# USBC_A.net
KiCad netlist of a schematic drawn in Altium Designer
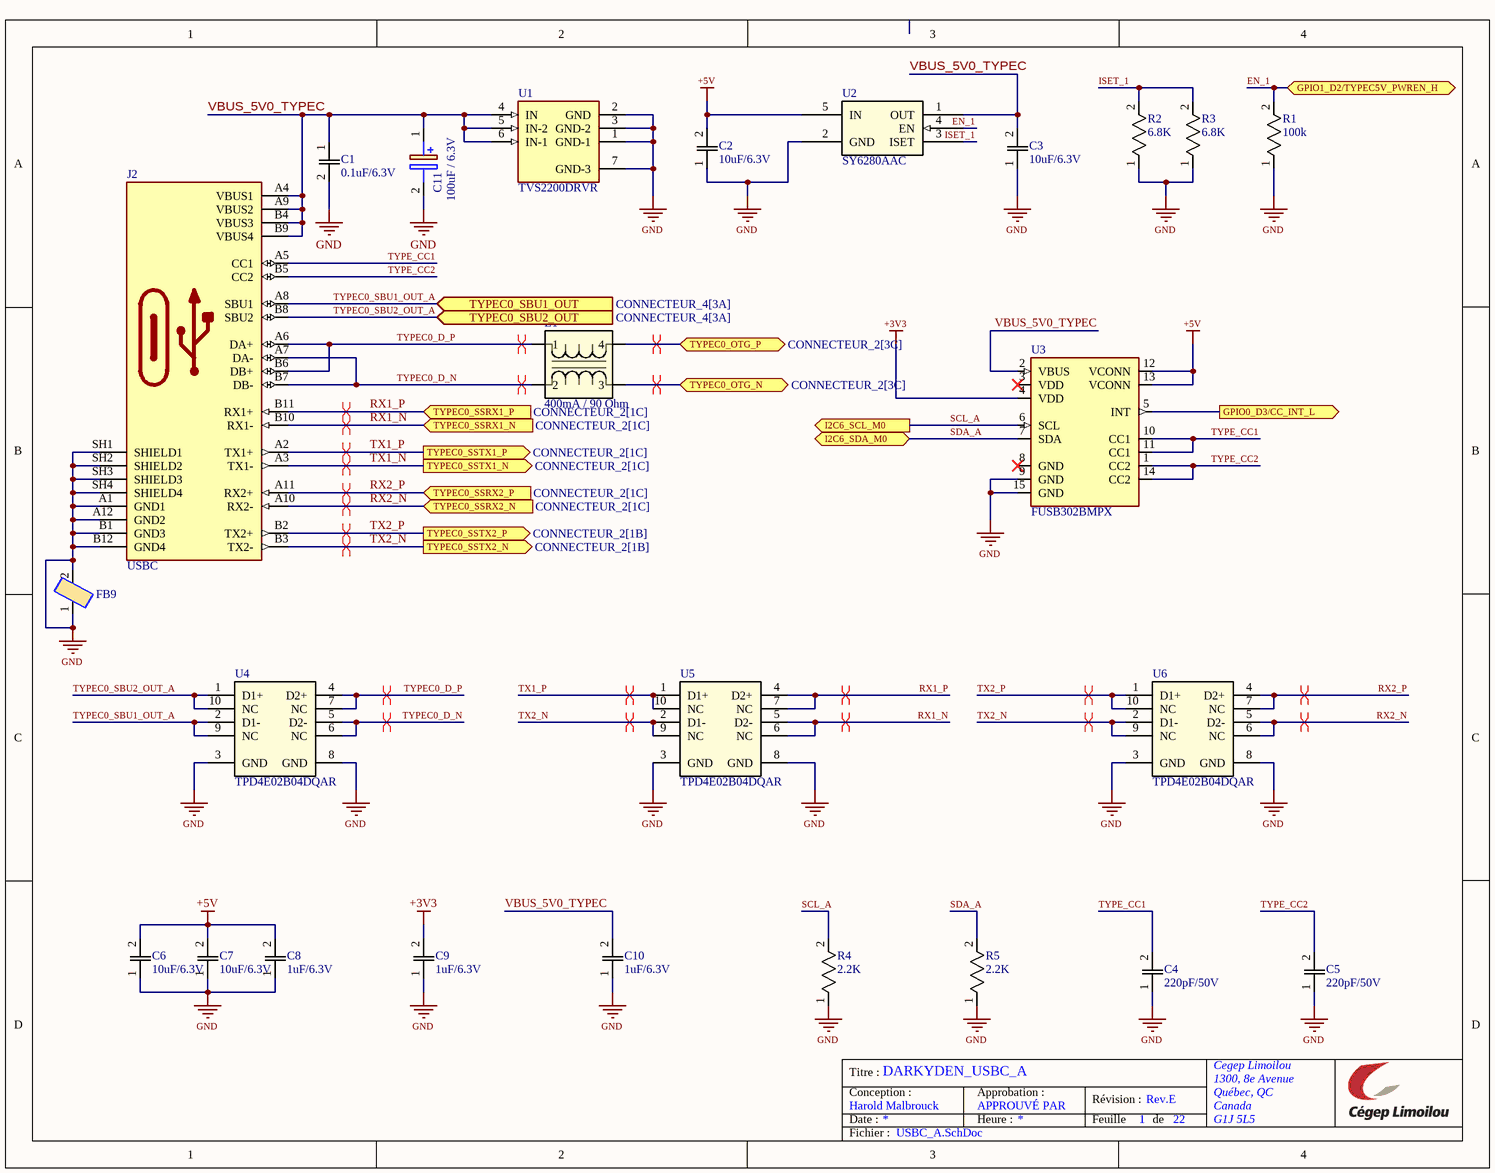
[diagram p0: USBC_A.SchDoc]

(export (version "E")
  (design (tool "Eeschema 10.0.6"))
  (components
    (comp (ref "C1")
      (value "0.1uF/6.3V")
      (footprint "SamacSys:C0805")
      (description "0.1uF 6.3V X7R 10% Pad SMD 0805 125C T/R")
      (fields
        (field (name "MANUFACTURER_PART_NUMBER") "C0805C104K9RACTU")
        (field (name "MOUSER PART NUMBER") "80-C0805C104K9R")
      )
      (libsource (lib "SamacSys") (part "C0805C104K9RACTU"))
    )
    (comp (ref "C2")
      (value "10uF/6.3V")
      (footprint "SamacSys:C0805")
      (fields
        (field (name "MANUFACTURER_PART_NUMBER") "C0805C106K9RACTU")
        (field (name "MOUSER PART NUMBER") "80-C0805C106K9R")
        (field (name "MANUFACTURER") "KEMET")
      )
      (libsource (lib "SamacSys") (part "C0805C106K9RACTU"))
    )
    (comp (ref "C3")
      (value "10uF/6.3V")
      (footprint "SamacSys:C0805")
      (fields
        (field (name "MANUFACTURER_PART_NUMBER") "C0805C106K9RACTU")
        (field (name "MOUSER PART NUMBER") "80-C0805C106K9R")
        (field (name "MANUFACTURER") "KEMET")
      )
      (libsource (lib "SamacSys") (part "C0805C106K9RACTU"))
    )
    (comp (ref "C4")
      (value "220pF/50V")
      (footprint "CAPC220145_88N_KEM")
      (description "Cap Ceramic 220pF 50V X7R 20% Pad SMD 0805 125C T/R")
      (fields
        (field (name "MANUFACTURER") "KEMET")
        (field (name "MANUFACTURER PART NUMBER") "C0805C221M5RACTU")
      )
      (libsource (lib "C0805C221M5RACTU") (part "C0805C221M5RACTU"))
    )
    (comp (ref "C5")
      (value "220pF/50V")
      (footprint "CAPC220145_88N_KEM")
      (description "Cap Ceramic 220pF 50V X7R 20% Pad SMD 0805 125C T/R")
      (fields
        (field (name "MANUFACTURER") "KEMET")
        (field (name "MANUFACTURER PART NUMBER") "C0805C221M5RACTU")
      )
      (libsource (lib "C0805C221M5RACTU") (part "C0805C221M5RACTU"))
    )
    (comp (ref "C6")
      (value "10uF/6.3V")
      (footprint "SamacSys:C0805")
      (fields
        (field (name "MANUFACTURER_PART_NUMBER") "C0805C106K9RACTU")
        (field (name "MOUSER PART NUMBER") "80-C0805C106K9R")
        (field (name "MANUFACTURER") "KEMET")
      )
      (libsource (lib "SamacSys") (part "C0805C106K9RACTU"))
    )
    (comp (ref "C7")
      (value "10uF/6.3V")
      (footprint "SamacSys:C0805")
      (fields
        (field (name "MANUFACTURER_PART_NUMBER") "C0805C106K9RACTU")
        (field (name "MOUSER PART NUMBER") "80-C0805C106K9R")
        (field (name "MANUFACTURER") "KEMET")
      )
      (libsource (lib "SamacSys") (part "C0805C106K9RACTU"))
    )
    (comp (ref "C8")
      (value "1uF/6.3V")
      (footprint "SamacSys:C0805")
      (description "1 uF, 6.3 V, ± 10%, X7R, 0805 [2012 Metric] Multilayer Ceramic Capacitor,")
      (fields
        (field (name "MANUFACTURER_PART_NUMBER") "C0805C105K9RACTU")
        (field (name "MOUSER PART NUMBER") "80-C0805C105K9R")
      )
      (libsource (lib "SamacSys") (part "C0805C105K9RACTU"))
    )
    (comp (ref "C9")
      (value "1uF/6.3V")
      (footprint "SamacSys:C0805")
      (description "1 uF, 6.3 V, ± 10%, X7R, 0805 [2012 Metric] Multilayer Ceramic Capacitor,")
      (fields
        (field (name "MANUFACTURER_PART_NUMBER") "C0805C105K9RACTU")
        (field (name "MOUSER PART NUMBER") "80-C0805C105K9R")
      )
      (libsource (lib "SamacSys") (part "C0805C105K9RACTU"))
    )
    (comp (ref "C10")
      (value "1uF/6.3V")
      (footprint "SamacSys:C0805")
      (description "1 uF, 6.3 V, ± 10%, X7R, 0805 [2012 Metric] Multilayer Ceramic Capacitor,")
      (fields
        (field (name "MANUFACTURER_PART_NUMBER") "C0805C105K9RACTU")
        (field (name "MOUSER PART NUMBER") "80-C0805C105K9R")
      )
      (libsource (lib "SamacSys") (part "C0805C105K9RACTU"))
    )
    (comp (ref "C11")
      (value "100uF / 6.3V")
      (footprint "SamacSys:EEE0GA101SR")
      (description "100uF 6.3V 20% Cap Aluminum Lytic  SMD 0.36 Ohm 240mA 2000h 105C Automotive T/R")
      (fields
        (field (name "MANUFACTURER_PART_NUMBER") "EEE-FPJ101UAR")
        (field (name "MOUSER PART NUMBER") "667-EEE-FPJ101UAR")
      )
      (libsource (lib "SamacSys") (part "EEE-FPJ101UAR"))
    )
    (comp (ref "FB9")
      (value "220R / 100MHz")
      (footprint "SamacSys:BLM18SP221SN1B")
      (description "Ferrite Beads Multi-Layer 220Ohm 25% 100MHz 2A 50mOhm DCR 0603 Paper T/R")
      (fields
        (field (name "MANUFACTURER_PART_NUMBER") "BLM18EG221SN1D")
        (field (name "MOUSER PART NUMBER") "81-BLM18EG221SN1D")
      )
      (libsource (lib "SamacSys") (part "BLM18EG221SN1D"))
    )
    (comp (ref "J2")
      (value "USBC")
      (footprint "MOLEX_2012670005")
      (fields (field (name "MF") "Molex") (field (name "MP") "2012670005"))
      (libsource (lib "USBC") (part "USBC"))
    )
    (comp (ref "L1")
      (value "400mA / 90 Ohm")
      (footprint "SamacSys:ACM20129002PT002")
      (description "Ferrite Beads Wirewound Common Mode Filter 90Ohm 100MHz 400mA 0805 T/R")
      (fields
        (field (name "MANUFACTURER_PART_NUMBER") "ACM2012-900-2P-T002")
        (field (name "MOUSER PART NUMBER") "810-ACM20129002PT002")
      )
      (libsource (lib "SamacSys") (part "ACM2012-900-2P-T002"))
    )
    (comp (ref "R1")
      (value "100k")
      (footprint "SamacSys:ERJ3EKF1000V")
      (description "100K Ohm 5%  Res Thick Film 0603 1/10W +/-200ppm/ßC Molded SMD Punched Carrier T/R")
      (fields
        (field (name "MANUFACTURER_PART_NUMBER") "ERJ-3GEYJ104V")
        (field (name "MOUSER PART NUMBER") "667-ERJ-3GEYJ104V")
      )
      (libsource (lib "SamacSys") (part "ERJ-3GEYJ104V"))
    )
    (comp (ref "R2")
      (value "6.8K")
      (footprint "SamacSys:ERJ3EKF1000V")
      (description "6.8 kOhm, ± 5%, 100 mW, 0603 [1608 Metric], Thick Film, General Purpose")
      (fields
        (field (name "MANUFACTURER_PART_NUMBER") "ERJ-3GEYJ682V")
        (field (name "MANUFACTURER") "Panasonic")
      )
      (libsource (lib "SamacSys") (part "ERJ-3GEYJ682V"))
    )
    (comp (ref "R3")
      (value "6.8K")
      (footprint "SamacSys:ERJ3EKF1000V")
      (description "6.8 kOhm, ± 5%, 100 mW, 0603 [1608 Metric], Thick Film, General Purpose")
      (fields
        (field (name "MANUFACTURER_PART_NUMBER") "ERJ-3GEYJ682V")
        (field (name "MANUFACTURER") "Panasonic")
      )
      (libsource (lib "SamacSys") (part "ERJ-3GEYJ682V"))
    )
    (comp (ref "R4")
      (value "2.2K")
      (footprint "SamacSys:ERJ3EKF1000V")
      (description "2.2 kOhm, ï¿½ 5%, 100 mW, 0603 [1608 Metric], Thick Film, General Purpose")
      (fields
        (field (name "MANUFACTURER_PART_NUMBER") "ERJ-3GEYJ222V")
        (field (name "MOUSER PART NUMBER") "667-ERJ-3GEYJ222V")
      )
      (libsource (lib "SamacSys") (part "ERJ-3GEYJ222V"))
    )
    (comp (ref "R5")
      (value "2.2K")
      (footprint "SamacSys:ERJ3EKF1000V")
      (description "2.2 kOhm, ï¿½ 5%, 100 mW, 0603 [1608 Metric], Thick Film, General Purpose")
      (fields
        (field (name "MANUFACTURER_PART_NUMBER") "ERJ-3GEYJ222V")
        (field (name "MOUSER PART NUMBER") "667-ERJ-3GEYJ222V")
      )
      (libsource (lib "SamacSys") (part "ERJ-3GEYJ222V"))
    )
    (comp (ref "U1")
      (value "TVS2200DRVR")
      (footprint "SON65P200X200X80-7N")
      (description "ESD Suppressors / TVS Diodes 22V flat-clamp surge protection device 6-WSON -40 to 125")
      (fields (field (name "MF") "Texas Instruments"))
      (libsource (lib "TVS2200") (part "TVS2200DRVR"))
    )
    (comp (ref "U2")
      (value "SY6280AAC")
      (footprint "SamacSys:SOT95P285X140-5N")
      (description "2.4V~5.5V 80mΩ Active High 1 High-side switch SOT-23-5 Power Distribution Switches ROHS")
      (libsource (lib "SamacSys") (part "SY6280AAC"))
    )
    (comp (ref "U3")
      (value "FUSB302BMPX")
      (footprint "SamacSys:QFN50P250X250X80-15N")
      (description "USB Controller USB 3.1 USB Interface 14-MLP (2.5x2.5)")
      (fields (field (name "MOUSER PART NUMBER") "512-FUSB302BMPX"))
      (libsource (lib "SamacSys") (part "FUSB302BMPX"))
    )
    (comp (ref "U4")
      (value "TPD4E02B04DQAR")
      (footprint "DQA0010A")
      (description "TVS DIODE 3.6V 8.8V 10USON / 4-Channel ESD Protection Diode for USB Type-C and HDMI 2.0")
      (fields (field (name "MANUFACTURER") "Texas Instruments"))
      (libsource (lib "TPD4E02B04DQAR") (part "TPD4E02B04DQAR"))
    )
    (comp (ref "U5")
      (value "TPD4E02B04DQAR")
      (footprint "DQA0010A")
      (description "TVS DIODE 3.6V 8.8V 10USON / 4-Channel ESD Protection Diode for USB Type-C and HDMI 2.0")
      (fields (field (name "MANUFACTURER") "Texas Instruments"))
      (libsource (lib "TPD4E02B04DQAR") (part "TPD4E02B04DQAR"))
    )
    (comp (ref "U6")
      (value "TPD4E02B04DQAR")
      (footprint "DQA0010A")
      (description "TVS DIODE 3.6V 8.8V 10USON / 4-Channel ESD Protection Diode for USB Type-C and HDMI 2.0")
      (fields (field (name "MANUFACTURER") "Texas Instruments"))
      (libsource (lib "TPD4E02B04DQAR") (part "TPD4E02B04DQAR"))
    )
  )
  (nets
    (net (code "1") (name "+3V3") (class "Default")
      (node (ref "C9") (pin "2") (pinfunction "2_2") (pintype "passive"))
      (node (ref "U3") (pin "4") (pinfunction "VDD_4") (pintype "power_in"))
    )
    (net (code "2") (name "+5V") (class "Default")
      (node (ref "C2") (pin "2") (pinfunction "2_2") (pintype "passive"))
      (node (ref "C6") (pin "2") (pinfunction "2_2") (pintype "passive"))
      (node (ref "C7") (pin "2") (pinfunction "2_2") (pintype "passive"))
      (node (ref "C8") (pin "2") (pinfunction "2_2") (pintype "passive"))
      (node (ref "U2") (pin "5") (pinfunction "IN_5") (pintype "power_in"))
      (node (ref "U3") (pin "12") (pinfunction "VCONN_12") (pintype "power_in"))
      (node (ref "U3") (pin "13") (pinfunction "VCONN_13") (pintype "power_in"))
    )
    (net (code "3") (name "/EN_1") (class "Default")
      (node (ref "R1") (pin "2") (pinfunction "2_2") (pintype "passive"))
      (node (ref "U2") (pin "4") (pinfunction "EN_4") (pintype "input"))
    )
    (net (code "4") (name "/GPIO0_D3{slash}CC_INT_L") (class "Default")
      (node (ref "U3") (pin "5") (pinfunction "INT_5") (pintype "output"))
    )
    (net (code "5") (name "/ISET_1") (class "Default")
      (node (ref "R2") (pin "2") (pinfunction "2_2") (pintype "passive"))
      (node (ref "R3") (pin "2") (pinfunction "2_2") (pintype "passive"))
      (node (ref "U2") (pin "3") (pinfunction "ISET_3") (pintype "passive"))
    )
    (net (code "6") (name "/RX1_N") (class "Default")
      (node (ref "J2") (pin "B10") (pinfunction "RX1-_B10") (pintype "input"))
      (node (ref "U5") (pin "5") (pinfunction "D2-_5") (pintype "passive"))
      (node (ref "U5") (pin "6") (pinfunction "NC_6") (pintype "passive"))
    )
    (net (code "7") (name "/RX1_P") (class "Default")
      (node (ref "J2") (pin "B11") (pinfunction "RX1+_B11") (pintype "input"))
      (node (ref "U5") (pin "4") (pinfunction "D2+_4") (pintype "passive"))
      (node (ref "U5") (pin "7") (pinfunction "NC_7") (pintype "passive"))
    )
    (net (code "8") (name "/RX2_N") (class "Default")
      (node (ref "J2") (pin "A10") (pinfunction "RX2-_A10") (pintype "input"))
      (node (ref "U6") (pin "5") (pinfunction "D2-_5") (pintype "passive"))
      (node (ref "U6") (pin "6") (pinfunction "NC_6") (pintype "passive"))
    )
    (net (code "9") (name "/RX2_P") (class "Default")
      (node (ref "J2") (pin "A11") (pinfunction "RX2+_A11") (pintype "input"))
      (node (ref "U6") (pin "4") (pinfunction "D2+_4") (pintype "passive"))
      (node (ref "U6") (pin "7") (pinfunction "NC_7") (pintype "passive"))
    )
    (net (code "10") (name "/SCL_A") (class "Default")
      (node (ref "R4") (pin "2") (pinfunction "2_2") (pintype "passive"))
      (node (ref "U3") (pin "6") (pinfunction "SCL_6") (pintype "input"))
    )
    (net (code "11") (name "/SDA_A") (class "Default")
      (node (ref "R5") (pin "2") (pinfunction "2_2") (pintype "passive"))
      (node (ref "U3") (pin "7") (pinfunction "SDA_7") (pintype "bidirectional"))
    )
    (net (code "12") (name "/TX1_N") (class "Default")
      (node (ref "J2") (pin "A3") (pinfunction "TX1-_A3") (pintype "output"))
    )
    (net (code "13") (name "/TX1_P") (class "Default")
      (node (ref "J2") (pin "A2") (pinfunction "TX1+_A2") (pintype "output"))
      (node (ref "U5") (pin "1") (pinfunction "D1+_1") (pintype "passive"))
      (node (ref "U5") (pin "10") (pinfunction "NC_10") (pintype "passive"))
    )
    (net (code "14") (name "/TX2_N") (class "Default")
      (node (ref "J2") (pin "B3") (pinfunction "TX2-_B3") (pintype "output"))
      (node (ref "U5") (pin "2") (pinfunction "D1-_2") (pintype "passive"))
      (node (ref "U5") (pin "9") (pinfunction "NC_9") (pintype "passive"))
      (node (ref "U6") (pin "2") (pinfunction "D1-_2") (pintype "passive"))
      (node (ref "U6") (pin "9") (pinfunction "NC_9") (pintype "passive"))
    )
    (net (code "15") (name "/TX2_P") (class "Default")
      (node (ref "J2") (pin "B2") (pinfunction "TX2+_B2") (pintype "output"))
      (node (ref "U6") (pin "1") (pinfunction "D1+_1") (pintype "passive"))
      (node (ref "U6") (pin "10") (pinfunction "NC_10") (pintype "passive"))
    )
    (net (code "16") (name "/TYPEC0_D_N") (class "Default")
      (node (ref "J2") (pin "A7") (pinfunction "DA-_A7") (pintype "bidirectional"))
      (node (ref "J2") (pin "B7") (pinfunction "DB-_B7") (pintype "bidirectional"))
      (node (ref "L1") (pin "2") (pinfunction "2_2") (pintype "passive"))
      (node (ref "U4") (pin "5") (pinfunction "D2-_5") (pintype "passive"))
      (node (ref "U4") (pin "6") (pinfunction "NC_6") (pintype "passive"))
    )
    (net (code "17") (name "/TYPEC0_D_P") (class "Default")
      (node (ref "J2") (pin "A6") (pinfunction "DA+_A6") (pintype "bidirectional"))
      (node (ref "J2") (pin "B6") (pinfunction "DB+_B6") (pintype "bidirectional"))
      (node (ref "L1") (pin "1") (pinfunction "1_1") (pintype "passive"))
      (node (ref "U4") (pin "4") (pinfunction "D2+_4") (pintype "passive"))
      (node (ref "U4") (pin "7") (pinfunction "NC_7") (pintype "passive"))
    )
    (net (code "18") (name "/TYPEC0_OTG_N") (class "Default")
      (node (ref "L1") (pin "3") (pinfunction "3_3") (pintype "passive"))
    )
    (net (code "19") (name "/TYPEC0_OTG_P") (class "Default")
      (node (ref "L1") (pin "4") (pinfunction "4_4") (pintype "passive"))
    )
    (net (code "20") (name "/TYPEC0_SBU1_OUT_A") (class "Default")
      (node (ref "J2") (pin "A8") (pinfunction "SBU1_A8") (pintype "bidirectional"))
      (node (ref "U4") (pin "2") (pinfunction "D1-_2") (pintype "passive"))
      (node (ref "U4") (pin "9") (pinfunction "NC_9") (pintype "passive"))
    )
    (net (code "21") (name "/TYPEC0_SBU2_OUT_A") (class "Default")
      (node (ref "J2") (pin "B8") (pinfunction "SBU2_B8") (pintype "bidirectional"))
      (node (ref "U4") (pin "1") (pinfunction "D1+_1") (pintype "passive"))
      (node (ref "U4") (pin "10") (pinfunction "NC_10") (pintype "passive"))
    )
    (net (code "22") (name "/TYPE_CC1") (class "Default")
      (node (ref "C4") (pin "2") (pinfunction "2_2") (pintype "passive"))
      (node (ref "J2") (pin "A5") (pinfunction "CC1_A5") (pintype "bidirectional"))
      (node (ref "U3") (pin "10") (pinfunction "CC1_10") (pintype "bidirectional"))
      (node (ref "U3") (pin "11") (pinfunction "CC1_11") (pintype "bidirectional"))
    )
    (net (code "23") (name "/TYPE_CC2") (class "Default")
      (node (ref "C5") (pin "2") (pinfunction "2_2") (pintype "passive"))
      (node (ref "J2") (pin "B5") (pinfunction "CC2_B5") (pintype "bidirectional"))
      (node (ref "U3") (pin "1") (pinfunction "CC2_1") (pintype "bidirectional"))
      (node (ref "U3") (pin "14") (pinfunction "CC2_14") (pintype "bidirectional"))
    )
    (net (code "24") (name "/VBUS_5V0_TYPEC") (class "Default")
      (node (ref "C1") (pin "1") (pinfunction "1_1") (pintype "passive"))
      (node (ref "C10") (pin "2") (pinfunction "2_2") (pintype "passive"))
      (node (ref "C11") (pin "1") (pinfunction "+_1") (pintype "passive"))
      (node (ref "C3") (pin "2") (pinfunction "2_2") (pintype "passive"))
      (node (ref "J2") (pin "A4") (pinfunction "VBUS1_A4") (pintype "power_in"))
      (node (ref "J2") (pin "A9") (pinfunction "VBUS2_A9") (pintype "power_in"))
      (node (ref "J2") (pin "B4") (pinfunction "VBUS3_B4") (pintype "power_in"))
      (node (ref "J2") (pin "B9") (pinfunction "VBUS4_B9") (pintype "power_in"))
      (node (ref "U1") (pin "4") (pinfunction "IN_4") (pintype "input"))
      (node (ref "U1") (pin "5") (pinfunction "IN-2_5") (pintype "input"))
      (node (ref "U1") (pin "6") (pinfunction "IN-1_6") (pintype "input"))
      (node (ref "U2") (pin "1") (pinfunction "OUT_1") (pintype "power_in"))
      (node (ref "U3") (pin "2") (pinfunction "VBUS_2") (pintype "input"))
    )
    (net (code "25") (name "GND") (class "Default")
      (node (ref "C1") (pin "2") (pinfunction "2_2") (pintype "passive"))
      (node (ref "C10") (pin "1") (pinfunction "1_1") (pintype "passive"))
      (node (ref "C11") (pin "2") (pinfunction "-_2") (pintype "passive"))
      (node (ref "C2") (pin "1") (pinfunction "1_1") (pintype "passive"))
      (node (ref "C3") (pin "1") (pinfunction "1_1") (pintype "passive"))
      (node (ref "C4") (pin "1") (pinfunction "1_1") (pintype "passive"))
      (node (ref "C5") (pin "1") (pinfunction "1_1") (pintype "passive"))
      (node (ref "C6") (pin "1") (pinfunction "1_1") (pintype "passive"))
      (node (ref "C7") (pin "1") (pinfunction "1_1") (pintype "passive"))
      (node (ref "C8") (pin "1") (pinfunction "1_1") (pintype "passive"))
      (node (ref "C9") (pin "1") (pinfunction "1_1") (pintype "passive"))
      (node (ref "FB9") (pin "1") (pinfunction "1_1") (pintype "passive"))
      (node (ref "FB9") (pin "2") (pinfunction "2_2") (pintype "passive"))
      (node (ref "J2") (pin "A1") (pinfunction "GND1_A1") (pintype "passive"))
      (node (ref "J2") (pin "A12") (pinfunction "GND2_A12") (pintype "passive"))
      (node (ref "J2") (pin "B1") (pinfunction "GND3_B1") (pintype "passive"))
      (node (ref "J2") (pin "B12") (pinfunction "GND4_B12") (pintype "passive"))
      (node (ref "J2") (pin "SH1") (pinfunction "SHIELD1_SH1") (pintype "passive"))
      (node (ref "J2") (pin "SH2") (pinfunction "SHIELD2_SH2") (pintype "passive"))
      (node (ref "J2") (pin "SH3") (pinfunction "SHIELD3_SH3") (pintype "passive"))
      (node (ref "J2") (pin "SH4") (pinfunction "SHIELD4_SH4") (pintype "passive"))
      (node (ref "R1") (pin "1") (pinfunction "1_1") (pintype "passive"))
      (node (ref "R2") (pin "1") (pinfunction "1_1") (pintype "passive"))
      (node (ref "R3") (pin "1") (pinfunction "1_1") (pintype "passive"))
      (node (ref "R4") (pin "1") (pinfunction "1_1") (pintype "passive"))
      (node (ref "R5") (pin "1") (pinfunction "1_1") (pintype "passive"))
      (node (ref "U1") (pin "1") (pinfunction "GND-1_1") (pintype "passive"))
      (node (ref "U1") (pin "2") (pinfunction "GND_2") (pintype "passive"))
      (node (ref "U1") (pin "3") (pinfunction "GND-2_3") (pintype "passive"))
      (node (ref "U1") (pin "7") (pinfunction "GND-3_7") (pintype "passive"))
      (node (ref "U2") (pin "2") (pinfunction "GND_2") (pintype "passive"))
      (node (ref "U3") (pin "15") (pinfunction "GND_15") (pintype "passive"))
      (node (ref "U3") (pin "9") (pinfunction "GND_9") (pintype "passive"))
      (node (ref "U4") (pin "3") (pinfunction "GND_3") (pintype "passive"))
      (node (ref "U4") (pin "8") (pinfunction "GND_8") (pintype "passive"))
      (node (ref "U5") (pin "3") (pinfunction "GND_3") (pintype "passive"))
      (node (ref "U5") (pin "8") (pinfunction "GND_8") (pintype "passive"))
      (node (ref "U6") (pin "3") (pinfunction "GND_3") (pintype "passive"))
      (node (ref "U6") (pin "8") (pinfunction "GND_8") (pintype "passive"))
    )
    (net (code "26") (name "unconnected-(U3-GND-Pad8)") (class "Default")
      (node (ref "U3") (pin "8") (pinfunction "GND_8") (pintype "passive+no_connect"))
    )
    (net (code "27") (name "unconnected-(U3-VDD-Pad3)") (class "Default")
      (node (ref "U3") (pin "3") (pinfunction "VDD_3") (pintype "power_in+no_connect"))
    )
  )
)
